# Carte_Asservissement.net
KiCad netlist of a schematic drawn in EAGLE
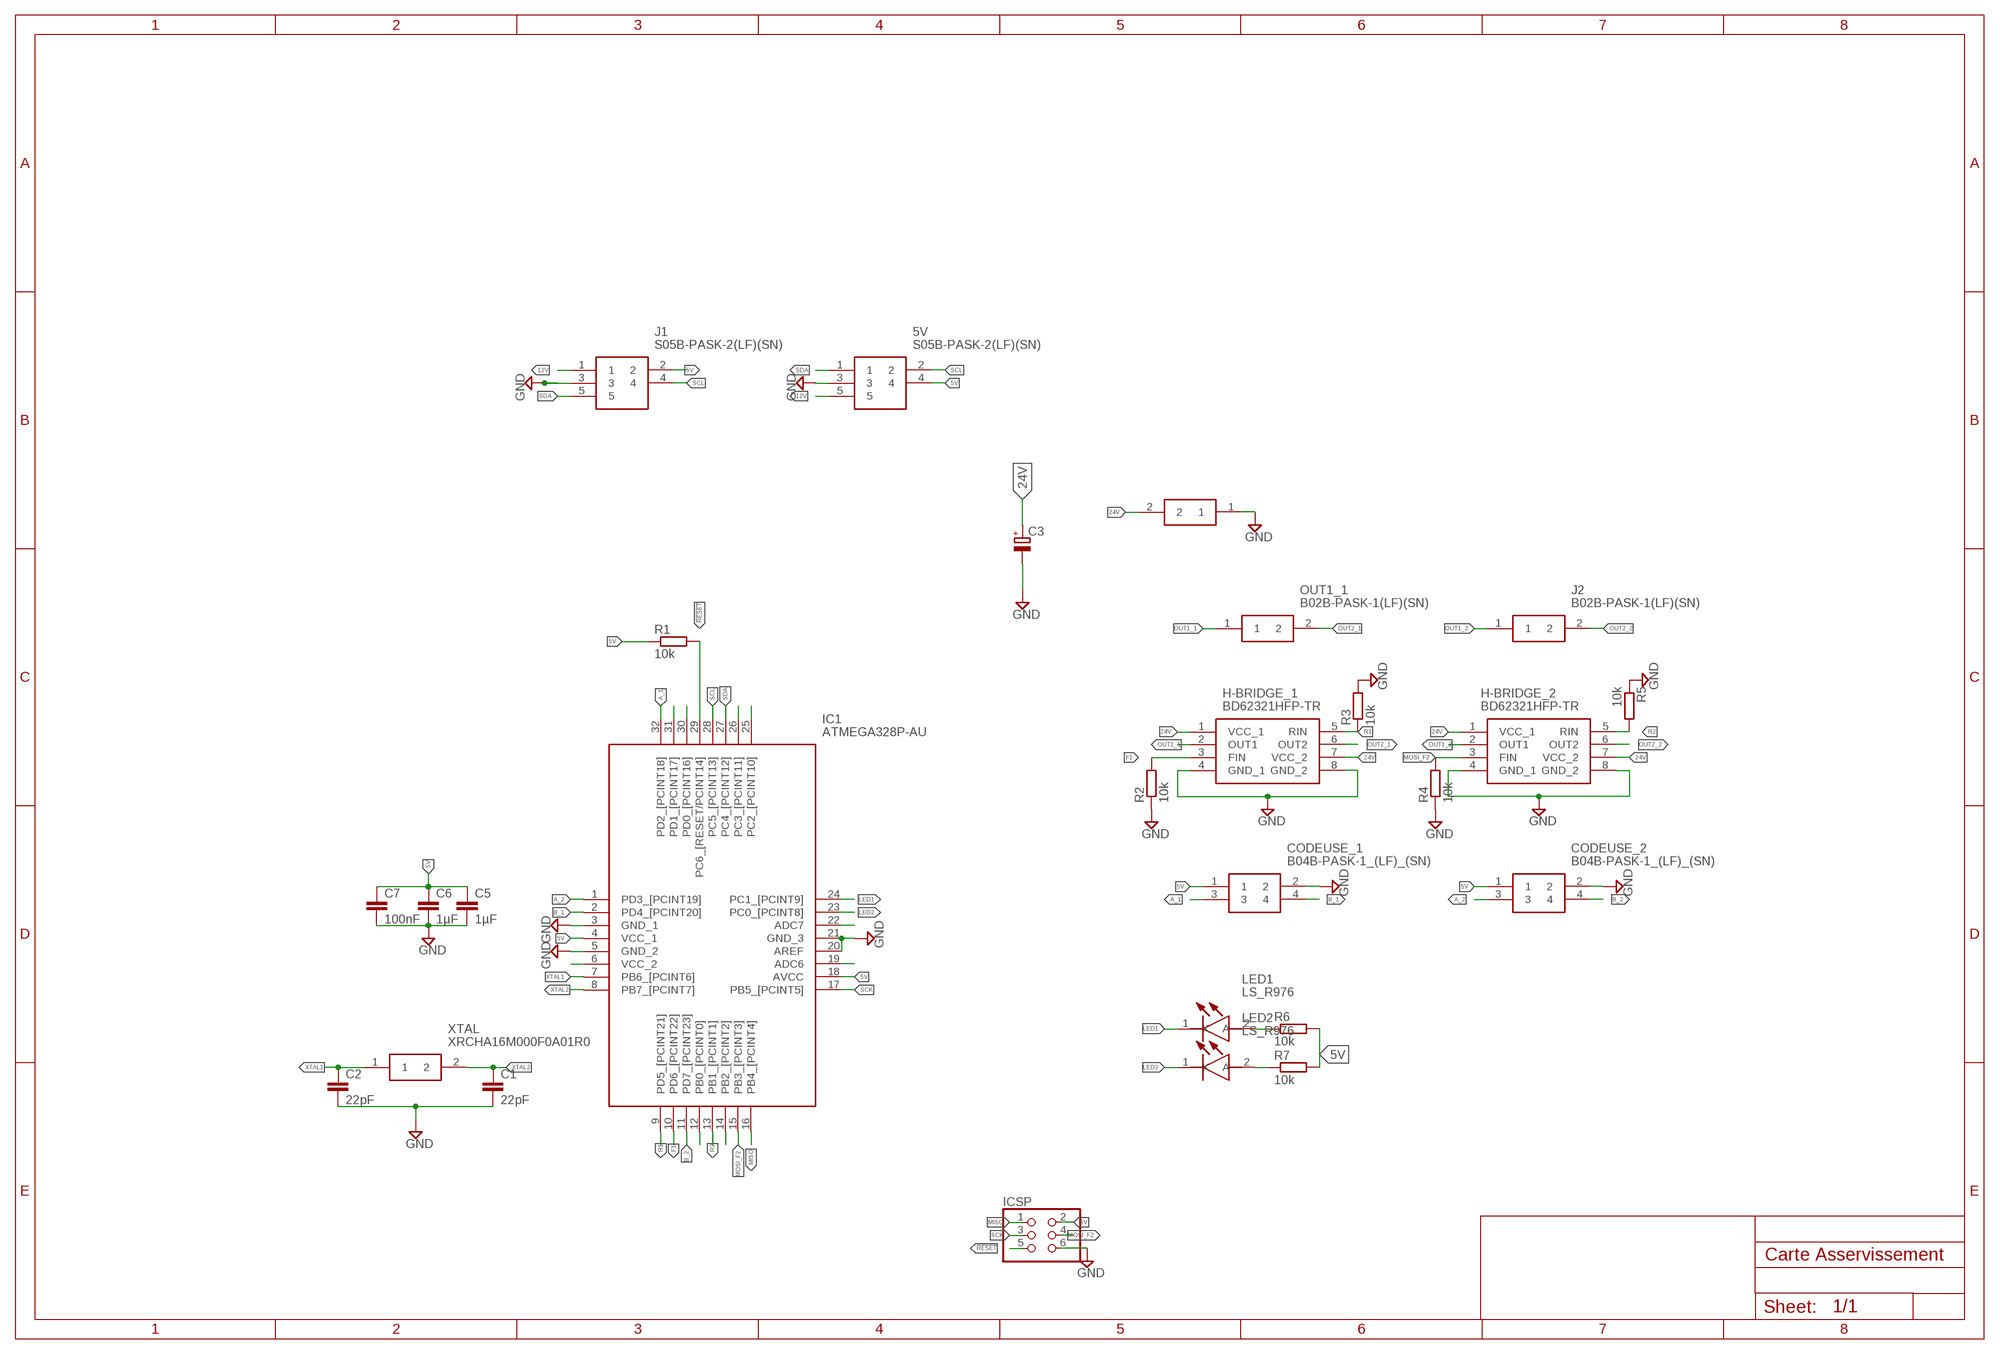
[diagram p0: schematic, sheet 1]

(export (version "E")
  (design (tool "Eeschema 10.0.6"))
  (components
    (comp (ref "5V")
      (value "S05B-PASK-2(LF)(SN)")
      (footprint "eagle-import:S05B-PASK-2(LF)(SN)")
      (libsource (lib "eagle-import") (part "S05B-PASK-2(LF)(SN)"))
    )
    (comp (ref "C1")
      (value "22pF")
      (footprint "eagle-import:C0805")
      (libsource (lib "eagle-import") (part "C-EUC0805"))
    )
    (comp (ref "C2")
      (value "22pF")
      (footprint "eagle-import:C0805")
      (libsource (lib "eagle-import") (part "C-EUC0805"))
    )
    (comp (ref "C3")
      (value "CPOL-EUSANYO_SMD_C6")
      (footprint "eagle-import:SANYO-OSCON_SMD_C6")
      (libsource (lib "eagle-import") (part "CPOL-EUSANYO_SMD_C6"))
    )
    (comp (ref "C5")
      (value "1µF")
      (footprint "eagle-import:C0805")
      (libsource (lib "eagle-import") (part "C-EUC0805"))
    )
    (comp (ref "C6")
      (value "1µF")
      (footprint "eagle-import:C0805")
      (libsource (lib "eagle-import") (part "C-EUC0805"))
    )
    (comp (ref "C7")
      (value "100nF")
      (footprint "eagle-import:C0805")
      (libsource (lib "eagle-import") (part "C-EUC0805"))
    )
    (comp (ref "CODEUSE_1")
      (value "B04B-PASK-1_(LF)_(SN)")
      (footprint "eagle-import:B04B-PASK-1")
      (fields
        (field (name "MANUFACTURER_PART_NUMBER") "B04B-PASK-1 (LF) (SN)")
        (field (name "RS_PART_NUMBER") "5128608P")
      )
      (libsource (lib "eagle-import") (part "B04B-PASK-1_(LF)_(SN)"))
    )
    (comp (ref "CODEUSE_2")
      (value "B04B-PASK-1_(LF)_(SN)")
      (footprint "eagle-import:B04B-PASK-1")
      (fields
        (field (name "MANUFACTURER_PART_NUMBER") "B04B-PASK-1 (LF) (SN)")
        (field (name "RS_PART_NUMBER") "5128608P")
      )
      (libsource (lib "eagle-import") (part "B04B-PASK-1_(LF)_(SN)"))
    )
    (comp (ref "H-BRIDGE_1")
      (value "BD62321HFP-TR")
      (footprint "eagle-import:HRP7")
      (fields
        (field (name "MOUSER_PART_NUMBER") "755-BD62321HFP-TR")
        (field (name "RS_PART_NUMBER") "1246483P")
      )
      (libsource (lib "eagle-import") (part "BD62321HFP-TR"))
    )
    (comp (ref "H-BRIDGE_2")
      (value "BD62321HFP-TR")
      (footprint "eagle-import:HRP7")
      (fields
        (field (name "MOUSER_PART_NUMBER") "755-BD62321HFP-TR")
        (field (name "RS_PART_NUMBER") "1246483P")
      )
      (libsource (lib "eagle-import") (part "BD62321HFP-TR"))
    )
    (comp (ref "IC1")
      (value "ATMEGA328P-AU")
      (footprint "eagle-import:QFP80P900X900X120-32N")
      (fields
        (field (name "MOUSER_PART_NUMBER") "556-ATMEGA328P-AU")
        (field (name "RS_PART_NUMBER") "1310271P")
      )
      (libsource (lib "eagle-import") (part "ATMEGA328P-AU"))
    )
    (comp (ref "ICSP")
      (value "PINHD-2X3")
      (footprint "eagle-import:2X03")
      (libsource (lib "eagle-import") (part "PINHD-2X3"))
    )
    (comp (ref "J1")
      (value "S05B-PASK-2(LF)(SN)")
      (footprint "eagle-import:S05B-PASK-2(LF)(SN)")
      (libsource (lib "eagle-import") (part "S05B-PASK-2(LF)(SN)"))
    )
    (comp (ref "J2")
      (value "B02B-PASK-1(LF)(SN)")
      (footprint "eagle-import:B02BPASK1LFSN")
      (libsource (lib "eagle-import") (part "B02B-PASK-1(LF)(SN)"))
    )
    (comp (ref "LED1")
      (value "LS_R976")
      (footprint "eagle-import:LEDC2012X40N")
      (fields
        (field (name "MANUFACTURER_PART_NUMBER") "LS R976")
        (field (name "MOUSER_PART_NUMBER") "720-LSR976-NR-1")
        (field (name "RS_PART_NUMBER") "4974804P")
      )
      (libsource (lib "eagle-import") (part "LS_R976"))
    )
    (comp (ref "LED2")
      (value "LS_R976")
      (footprint "eagle-import:LEDC2012X40N")
      (fields
        (field (name "MANUFACTURER_PART_NUMBER") "LS R976")
        (field (name "MOUSER_PART_NUMBER") "720-LSR976-NR-1")
        (field (name "RS_PART_NUMBER") "4974804P")
      )
      (libsource (lib "eagle-import") (part "LS_R976"))
    )
    (comp (ref "OUT1_1")
      (value "B02B-PASK-1(LF)(SN)")
      (footprint "eagle-import:B02BPASK1LFSN")
      (libsource (lib "eagle-import") (part "B02B-PASK-1(LF)(SN)"))
    )
    (comp (ref "OUT1_2")
      (value "B02B-PASK-1(LF)(SN)")
      (footprint "eagle-import:B02BPASK1LFSN")
      (libsource (lib "eagle-import") (part "B02B-PASK-1(LF)(SN)"))
    )
    (comp (ref "R1")
      (value "10k")
      (footprint "eagle-import:R0805")
      (libsource (lib "eagle-import") (part "R-EU_R0805"))
    )
    (comp (ref "R2")
      (value "10k")
      (footprint "eagle-import:R0805")
      (libsource (lib "eagle-import") (part "R-EU_R0805"))
    )
    (comp (ref "R3")
      (value "10k")
      (footprint "eagle-import:R0805")
      (libsource (lib "eagle-import") (part "R-EU_R0805"))
    )
    (comp (ref "R4")
      (value "10k")
      (footprint "eagle-import:R0805")
      (libsource (lib "eagle-import") (part "R-EU_R0805"))
    )
    (comp (ref "R5")
      (value "10k")
      (footprint "eagle-import:R0805")
      (libsource (lib "eagle-import") (part "R-EU_R0805"))
    )
    (comp (ref "R6")
      (value "10k")
      (footprint "eagle-import:R0805")
      (libsource (lib "eagle-import") (part "R-EU_R0805"))
    )
    (comp (ref "R7")
      (value "10k")
      (footprint "eagle-import:R0805")
      (libsource (lib "eagle-import") (part "R-EU_R0805"))
    )
    (comp (ref "XTAL")
      (value "XRCHA16M000F0A01R0")
      (footprint "eagle-import:XRCHA")
      (fields
        (field (name "MOUSER_PART_NUMBER") "81-XRCHA16M000F0A1R0")
        (field (name "RS_PART_NUMBER") "1446622")
      )
      (libsource (lib "eagle-import") (part "XRCHA16M000F0A01R0"))
    )
  )
  (nets
    (net (code "1") (name "/~{RESET}") (class "Default")
      (node (ref "IC1") (pin "29") (pinfunction "PC6_[RESET/PCINT14]_29") (pintype "bidirectional"))
      (node (ref "ICSP") (pin "5") (pinfunction "5_5") (pintype "passive"))
      (node (ref "R1") (pin "2") (pinfunction "2_2") (pintype "passive"))
    )
    (net (code "2") (name "5V") (class "Default")
      (node (ref "5V") (pin "4") (pinfunction "4_4") (pintype "bidirectional"))
      (node (ref "C5") (pin "1") (pinfunction "1_1") (pintype "passive"))
      (node (ref "C6") (pin "1") (pinfunction "1_1") (pintype "passive"))
      (node (ref "C7") (pin "1") (pinfunction "1_1") (pintype "passive"))
      (node (ref "CODEUSE_1") (pin "1") (pinfunction "1_1") (pintype "bidirectional"))
      (node (ref "CODEUSE_2") (pin "1") (pinfunction "1_1") (pintype "bidirectional"))
      (node (ref "IC1") (pin "18") (pinfunction "AVCC_18") (pintype "power_in"))
      (node (ref "IC1") (pin "4") (pinfunction "VCC_1_4") (pintype "power_in"))
      (node (ref "ICSP") (pin "2") (pinfunction "2_2") (pintype "passive"))
      (node (ref "J1") (pin "2") (pinfunction "2_2") (pintype "bidirectional"))
      (node (ref "R1") (pin "1") (pinfunction "1_1") (pintype "passive"))
      (node (ref "R6") (pin "2") (pinfunction "2_2") (pintype "passive"))
      (node (ref "R7") (pin "2") (pinfunction "2_2") (pintype "passive"))
    )
    (net (code "3") (name "12V") (class "Default")
      (node (ref "5V") (pin "5") (pinfunction "5_5") (pintype "bidirectional"))
      (node (ref "J1") (pin "1") (pinfunction "1_1") (pintype "bidirectional"))
    )
    (net (code "4") (name "24V") (class "Default")
      (node (ref "C3") (pin "+") (pinfunction "+_+") (pintype "passive"))
      (node (ref "H-BRIDGE_1") (pin "1") (pinfunction "VCC_1_1") (pintype "bidirectional"))
      (node (ref "H-BRIDGE_1") (pin "7") (pinfunction "VCC_2_7") (pintype "bidirectional"))
      (node (ref "H-BRIDGE_2") (pin "1") (pinfunction "VCC_1_1") (pintype "bidirectional"))
      (node (ref "H-BRIDGE_2") (pin "7") (pinfunction "VCC_2_7") (pintype "bidirectional"))
      (node (ref "OUT1_2") (pin "2") (pinfunction "2_2") (pintype "bidirectional"))
    )
    (net (code "5") (name "A_1") (class "Default")
      (node (ref "CODEUSE_1") (pin "3") (pinfunction "3_3") (pintype "bidirectional"))
      (node (ref "IC1") (pin "32") (pinfunction "PD2_[PCINT18]_32") (pintype "bidirectional"))
    )
    (net (code "6") (name "A_2") (class "Default")
      (node (ref "CODEUSE_2") (pin "3") (pinfunction "3_3") (pintype "bidirectional"))
      (node (ref "IC1") (pin "1") (pinfunction "PD3_[PCINT19]_1") (pintype "bidirectional"))
    )
    (net (code "7") (name "B_1") (class "Default")
      (node (ref "CODEUSE_1") (pin "4") (pinfunction "4_4") (pintype "bidirectional"))
      (node (ref "IC1") (pin "2") (pinfunction "PD4_[PCINT20]_2") (pintype "bidirectional"))
    )
    (net (code "8") (name "B_2") (class "Default")
      (node (ref "CODEUSE_2") (pin "4") (pinfunction "4_4") (pintype "bidirectional"))
      (node (ref "IC1") (pin "11") (pinfunction "PD7_[PCINT23]_11") (pintype "bidirectional"))
    )
    (net (code "9") (name "F1") (class "Default")
      (node (ref "H-BRIDGE_1") (pin "3") (pinfunction "FIN_3") (pintype "bidirectional"))
      (node (ref "IC1") (pin "10") (pinfunction "PD6_[PCINT22]_10") (pintype "bidirectional"))
      (node (ref "R2") (pin "2") (pinfunction "2_2") (pintype "passive"))
    )
    (net (code "10") (name "GND") (class "Default")
      (node (ref "5V") (pin "3") (pinfunction "3_3") (pintype "bidirectional"))
      (node (ref "C1") (pin "2") (pinfunction "2_2") (pintype "passive"))
      (node (ref "C2") (pin "2") (pinfunction "2_2") (pintype "passive"))
      (node (ref "C3") (pin "-") (pinfunction "-_-") (pintype "passive"))
      (node (ref "C5") (pin "2") (pinfunction "2_2") (pintype "passive"))
      (node (ref "C6") (pin "2") (pinfunction "2_2") (pintype "passive"))
      (node (ref "C7") (pin "2") (pinfunction "2_2") (pintype "passive"))
      (node (ref "CODEUSE_1") (pin "2") (pinfunction "2_2") (pintype "bidirectional"))
      (node (ref "CODEUSE_2") (pin "2") (pinfunction "2_2") (pintype "bidirectional"))
      (node (ref "H-BRIDGE_1") (pin "4") (pinfunction "GND_1_4") (pintype "bidirectional"))
      (node (ref "H-BRIDGE_1") (pin "8") (pinfunction "GND_2_8") (pintype "bidirectional"))
      (node (ref "H-BRIDGE_2") (pin "4") (pinfunction "GND_1_4") (pintype "bidirectional"))
      (node (ref "H-BRIDGE_2") (pin "8") (pinfunction "GND_2_8") (pintype "bidirectional"))
      (node (ref "IC1") (pin "20") (pinfunction "AREF_20") (pintype "bidirectional"))
      (node (ref "IC1") (pin "21") (pinfunction "GND_3_21") (pintype "power_in"))
      (node (ref "IC1") (pin "3") (pinfunction "GND_1_3") (pintype "power_in"))
      (node (ref "IC1") (pin "5") (pinfunction "GND_2_5") (pintype "power_in"))
      (node (ref "ICSP") (pin "6") (pinfunction "6_6") (pintype "passive"))
      (node (ref "J1") (pin "3") (pinfunction "3_3") (pintype "bidirectional"))
      (node (ref "OUT1_2") (pin "1") (pinfunction "1_1") (pintype "bidirectional"))
      (node (ref "R2") (pin "1") (pinfunction "1_1") (pintype "passive"))
      (node (ref "R3") (pin "2") (pinfunction "2_2") (pintype "passive"))
      (node (ref "R4") (pin "1") (pinfunction "1_1") (pintype "passive"))
      (node (ref "R5") (pin "1") (pinfunction "1_1") (pintype "passive"))
    )
    (net (code "11") (name "LED1") (class "Default")
      (node (ref "IC1") (pin "24") (pinfunction "PC1_[PCINT9]_24") (pintype "bidirectional"))
      (node (ref "LED1") (pin "1") (pinfunction "K_1") (pintype "bidirectional"))
    )
    (net (code "12") (name "LED2") (class "Default")
      (node (ref "IC1") (pin "23") (pinfunction "PC0_[PCINT8]_23") (pintype "bidirectional"))
      (node (ref "LED2") (pin "1") (pinfunction "K_1") (pintype "bidirectional"))
    )
    (net (code "13") (name "MISO") (class "Default")
      (node (ref "IC1") (pin "16") (pinfunction "PB4_[PCINT4]_16") (pintype "bidirectional"))
      (node (ref "ICSP") (pin "1") (pinfunction "1_1") (pintype "passive"))
    )
    (net (code "14") (name "MOSI_F2") (class "Default")
      (node (ref "H-BRIDGE_2") (pin "3") (pinfunction "FIN_3") (pintype "bidirectional"))
      (node (ref "IC1") (pin "15") (pinfunction "PB3_[PCINT3]_15") (pintype "bidirectional"))
      (node (ref "ICSP") (pin "4") (pinfunction "4_4") (pintype "passive"))
      (node (ref "R4") (pin "2") (pinfunction "2_2") (pintype "passive"))
    )
    (net (code "15") (name "Net-(LED1-A)") (class "Default")
      (node (ref "LED1") (pin "2") (pinfunction "A_2") (pintype "bidirectional"))
      (node (ref "R6") (pin "1") (pinfunction "1_1") (pintype "passive"))
    )
    (net (code "16") (name "Net-(LED2-A)") (class "Default")
      (node (ref "LED2") (pin "2") (pinfunction "A_2") (pintype "bidirectional"))
      (node (ref "R7") (pin "1") (pinfunction "1_1") (pintype "passive"))
    )
    (net (code "17") (name "OUT1_1") (class "Default")
      (node (ref "H-BRIDGE_1") (pin "2") (pinfunction "OUT1_2") (pintype "bidirectional"))
      (node (ref "OUT1_1") (pin "1") (pinfunction "1_1") (pintype "bidirectional"))
    )
    (net (code "18") (name "OUT1_2") (class "Default")
      (node (ref "H-BRIDGE_2") (pin "2") (pinfunction "OUT1_2") (pintype "bidirectional"))
      (node (ref "J2") (pin "1") (pinfunction "1_1") (pintype "bidirectional"))
    )
    (net (code "19") (name "OUT2_1") (class "Default")
      (node (ref "H-BRIDGE_1") (pin "6") (pinfunction "OUT2_6") (pintype "bidirectional"))
      (node (ref "OUT1_1") (pin "2") (pinfunction "2_2") (pintype "bidirectional"))
    )
    (net (code "20") (name "OUT2_2") (class "Default")
      (node (ref "H-BRIDGE_2") (pin "6") (pinfunction "OUT2_6") (pintype "bidirectional"))
      (node (ref "J2") (pin "2") (pinfunction "2_2") (pintype "bidirectional"))
    )
    (net (code "21") (name "R1") (class "Default")
      (node (ref "H-BRIDGE_1") (pin "5") (pinfunction "RIN_5") (pintype "bidirectional"))
      (node (ref "IC1") (pin "9") (pinfunction "PD5_[PCINT21]_9") (pintype "bidirectional"))
      (node (ref "R3") (pin "1") (pinfunction "1_1") (pintype "passive"))
    )
    (net (code "22") (name "R2") (class "Default")
      (node (ref "H-BRIDGE_2") (pin "5") (pinfunction "RIN_5") (pintype "bidirectional"))
      (node (ref "IC1") (pin "13") (pinfunction "PB1_[PCINT1]_13") (pintype "bidirectional"))
      (node (ref "R5") (pin "2") (pinfunction "2_2") (pintype "passive"))
    )
    (net (code "23") (name "SCK") (class "Default")
      (node (ref "IC1") (pin "17") (pinfunction "PB5_[PCINT5]_17") (pintype "bidirectional"))
      (node (ref "ICSP") (pin "3") (pinfunction "3_3") (pintype "passive"))
    )
    (net (code "24") (name "SCL") (class "Default")
      (node (ref "5V") (pin "2") (pinfunction "2_2") (pintype "bidirectional"))
      (node (ref "IC1") (pin "28") (pinfunction "PC5_[PCINT13]_28") (pintype "bidirectional"))
      (node (ref "J1") (pin "4") (pinfunction "4_4") (pintype "bidirectional"))
    )
    (net (code "25") (name "SDA") (class "Default")
      (node (ref "5V") (pin "1") (pinfunction "1_1") (pintype "bidirectional"))
      (node (ref "IC1") (pin "27") (pinfunction "PC4_[PCINT12]_27") (pintype "bidirectional"))
      (node (ref "J1") (pin "5") (pinfunction "5_5") (pintype "bidirectional"))
    )
    (net (code "26") (name "XTAL1") (class "Default")
      (node (ref "C2") (pin "1") (pinfunction "1_1") (pintype "passive"))
      (node (ref "IC1") (pin "7") (pinfunction "PB6_[PCINT6]_7") (pintype "bidirectional"))
      (node (ref "XTAL") (pin "1") (pinfunction "1_1") (pintype "bidirectional"))
    )
    (net (code "27") (name "XTAL2") (class "Default")
      (node (ref "C1") (pin "1") (pinfunction "1_1") (pintype "passive"))
      (node (ref "IC1") (pin "8") (pinfunction "PB7_[PCINT7]_8") (pintype "bidirectional"))
      (node (ref "XTAL") (pin "2") (pinfunction "2_2") (pintype "bidirectional"))
    )
    (net (code "28") (name "unconnected-(IC1-ADC6-Pad19)") (class "Default")
      (node (ref "IC1") (pin "19") (pinfunction "ADC6_19") (pintype "bidirectional"))
    )
    (net (code "29") (name "unconnected-(IC1-ADC7-Pad22)") (class "Default")
      (node (ref "IC1") (pin "22") (pinfunction "ADC7_22") (pintype "bidirectional"))
    )
    (net (code "30") (name "unconnected-(IC1-PB0_[PCINT0]-Pad12)") (class "Default")
      (node (ref "IC1") (pin "12") (pinfunction "PB0_[PCINT0]_12") (pintype "bidirectional"))
    )
    (net (code "31") (name "unconnected-(IC1-PB2_[PCINT2]-Pad14)") (class "Default")
      (node (ref "IC1") (pin "14") (pinfunction "PB2_[PCINT2]_14") (pintype "bidirectional"))
    )
    (net (code "32") (name "unconnected-(IC1-PC2_[PCINT10]-Pad25)") (class "Default")
      (node (ref "IC1") (pin "25") (pinfunction "PC2_[PCINT10]_25") (pintype "bidirectional"))
    )
    (net (code "33") (name "unconnected-(IC1-PC3_[PCINT11]-Pad26)") (class "Default")
      (node (ref "IC1") (pin "26") (pinfunction "PC3_[PCINT11]_26") (pintype "bidirectional"))
    )
    (net (code "34") (name "unconnected-(IC1-PD0_[PCINT16]-Pad30)") (class "Default")
      (node (ref "IC1") (pin "30") (pinfunction "PD0_[PCINT16]_30") (pintype "bidirectional"))
    )
    (net (code "35") (name "unconnected-(IC1-PD1_[PCINT17]-Pad31)") (class "Default")
      (node (ref "IC1") (pin "31") (pinfunction "PD1_[PCINT17]_31") (pintype "bidirectional"))
    )
    (net (code "36") (name "unconnected-(IC1-VCC_2-Pad6)") (class "Default")
      (node (ref "IC1") (pin "6") (pinfunction "VCC_2_6") (pintype "power_in"))
    )
  )
)
